# Finger_Tremor_updated1107.net
KiCad netlist of a schematic drawn in Altium Designer
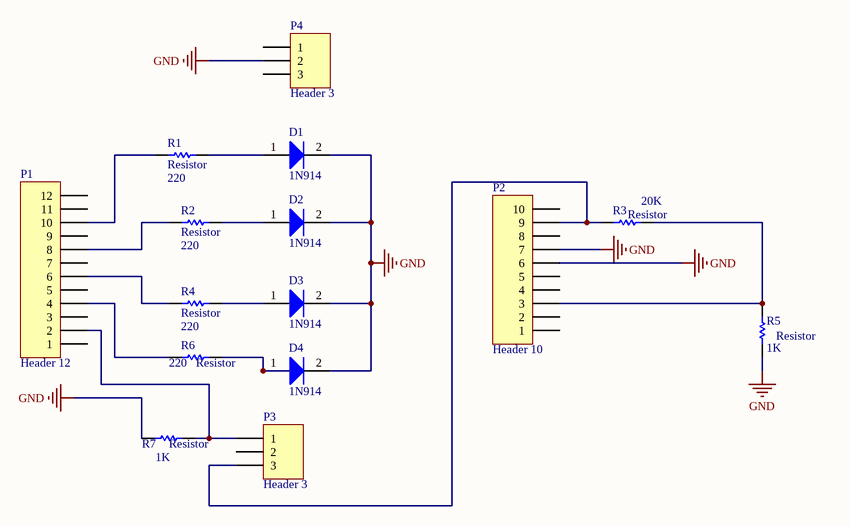
[diagram p0: Finger Tremor_updated1107.SchDoc]

(export (version "E")
  (design (tool "Eeschema 10.0.6"))
  (components
    (comp (ref "D1")
      (value "1N914")
      (footprint "Diode")
      (description "High Conductance Fast Diode")
      (libsource (lib "BME790Library") (part "1N914"))
    )
    (comp (ref "D2")
      (value "1N914")
      (footprint "Diode")
      (description "High Conductance Fast Diode")
      (libsource (lib "BME790Library") (part "1N914"))
    )
    (comp (ref "D3")
      (value "1N914")
      (footprint "Diode")
      (description "High Conductance Fast Diode")
      (libsource (lib "BME790Library") (part "1N914"))
    )
    (comp (ref "D4")
      (value "1N914")
      (footprint "Diode")
      (description "High Conductance Fast Diode")
      (libsource (lib "BME790Library") (part "1N914"))
    )
    (comp (ref "P1")
      (value "Header 12")
      (footprint "HDR1X12")
      (description "Header, 12-Pin")
      (fields (field (name "PUBLISHER") "Altium Limited"))
      (libsource (lib "Miscellaneous Connectors") (part "Header 12"))
    )
    (comp (ref "P2")
      (value "Header 10")
      (footprint "HDR1X10")
      (description "Header, 10-Pin")
      (fields (field (name "PUBLISHER") "Altium Limited"))
      (libsource (lib "Miscellaneous Connectors") (part "Header 10"))
    )
    (comp (ref "P3")
      (value "Header 3")
      (footprint "HDR1X3")
      (description "Header, 3-Pin")
      (fields (field (name "PUBLISHER") "Altium Limited"))
      (libsource (lib "Miscellaneous Connectors") (part "Header 3"))
    )
    (comp (ref "P4")
      (value "Header 3")
      (footprint "HDR1X3")
      (description "Header, 3-Pin")
      (fields (field (name "PUBLISHER") "Altium Limited"))
      (libsource (lib "Miscellaneous Connectors") (part "Header 3"))
    )
    (comp (ref "R1")
      (value "Resistor")
      (footprint "RES")
      (fields (field (name "ALTIUM_VALUE") "220"))
      (libsource (lib "BME790Library") (part "Resistor"))
    )
    (comp (ref "R2")
      (value "Resistor")
      (footprint "RES")
      (fields (field (name "ALTIUM_VALUE") "220"))
      (libsource (lib "BME790Library") (part "Resistor"))
    )
    (comp (ref "R3")
      (value "Resistor")
      (footprint "RES")
      (fields (field (name "ALTIUM_VALUE") "20K"))
      (libsource (lib "BME790Library") (part "Resistor"))
    )
    (comp (ref "R4")
      (value "Resistor")
      (footprint "RES")
      (fields (field (name "ALTIUM_VALUE") "220"))
      (libsource (lib "BME790Library") (part "Resistor"))
    )
    (comp (ref "R5")
      (value "Resistor")
      (footprint "RES")
      (fields (field (name "ALTIUM_VALUE") "1K"))
      (libsource (lib "BME790Library") (part "Resistor"))
    )
    (comp (ref "R6")
      (value "Resistor")
      (footprint "RES")
      (fields (field (name "ALTIUM_VALUE") "220"))
      (libsource (lib "BME790Library") (part "Resistor"))
    )
    (comp (ref "R7")
      (value "Resistor")
      (footprint "RES")
      (fields (field (name "ALTIUM_VALUE") "1K"))
      (libsource (lib "BME790Library") (part "Resistor"))
    )
  )
  (nets
    (net (code "1") (name "GND") (class "Default")
      (node (ref "D1") (pin "2") (pinfunction "K_2") (pintype "passive"))
      (node (ref "D2") (pin "2") (pinfunction "K_2") (pintype "passive"))
      (node (ref "D3") (pin "2") (pinfunction "K_2") (pintype "passive"))
      (node (ref "D4") (pin "2") (pinfunction "K_2") (pintype "passive"))
      (node (ref "P2") (pin "6") (pinfunction "6_6") (pintype "passive"))
      (node (ref "P2") (pin "7") (pinfunction "7_7") (pintype "passive"))
      (node (ref "P4") (pin "2") (pinfunction "2_2") (pintype "passive"))
      (node (ref "R5") (pin "1") (pinfunction "1_1") (pintype "passive"))
      (node (ref "R7") (pin "1") (pinfunction "1_1") (pintype "passive"))
    )
    (net (code "2") (name "Net-(D1-A)") (class "Default")
      (node (ref "D1") (pin "1") (pinfunction "A_1") (pintype "passive"))
      (node (ref "R1") (pin "2") (pinfunction "2_2") (pintype "passive"))
    )
    (net (code "3") (name "Net-(D2-A)") (class "Default")
      (node (ref "D2") (pin "1") (pinfunction "A_1") (pintype "passive"))
      (node (ref "R2") (pin "2") (pinfunction "2_2") (pintype "passive"))
    )
    (net (code "4") (name "Net-(D3-A)") (class "Default")
      (node (ref "D3") (pin "1") (pinfunction "A_1") (pintype "passive"))
      (node (ref "R4") (pin "2") (pinfunction "2_2") (pintype "passive"))
    )
    (net (code "5") (name "Net-(D4-A)") (class "Default")
      (node (ref "D4") (pin "1") (pinfunction "A_1") (pintype "passive"))
      (node (ref "R6") (pin "2") (pinfunction "2_2") (pintype "passive"))
    )
    (net (code "6") (name "Net-(P1-Pad2)") (class "Default")
      (node (ref "P1") (pin "2") (pinfunction "2_2") (pintype "passive"))
      (node (ref "P3") (pin "1") (pinfunction "1_1") (pintype "passive"))
      (node (ref "R7") (pin "2") (pinfunction "2_2") (pintype "passive"))
    )
    (net (code "7") (name "Net-(P1-Pad4)") (class "Default")
      (node (ref "P1") (pin "4") (pinfunction "4_4") (pintype "passive"))
      (node (ref "R6") (pin "1") (pinfunction "1_1") (pintype "passive"))
    )
    (net (code "8") (name "Net-(P1-Pad6)") (class "Default")
      (node (ref "P1") (pin "6") (pinfunction "6_6") (pintype "passive"))
      (node (ref "R4") (pin "1") (pinfunction "1_1") (pintype "passive"))
    )
    (net (code "9") (name "Net-(P1-Pad8)") (class "Default")
      (node (ref "P1") (pin "8") (pinfunction "8_8") (pintype "passive"))
      (node (ref "R2") (pin "1") (pinfunction "1_1") (pintype "passive"))
    )
    (net (code "10") (name "Net-(P1-Pad10)") (class "Default")
      (node (ref "P1") (pin "10") (pinfunction "10_10") (pintype "passive"))
      (node (ref "R1") (pin "1") (pinfunction "1_1") (pintype "passive"))
    )
    (net (code "11") (name "Net-(P2-Pad3)") (class "Default")
      (node (ref "P2") (pin "3") (pinfunction "3_3") (pintype "passive"))
      (node (ref "R3") (pin "2") (pinfunction "2_2") (pintype "passive"))
      (node (ref "R5") (pin "2") (pinfunction "2_2") (pintype "passive"))
    )
    (net (code "12") (name "Net-(P2-Pad9)") (class "Default")
      (node (ref "P2") (pin "9") (pinfunction "9_9") (pintype "passive"))
      (node (ref "P3") (pin "3") (pinfunction "3_3") (pintype "passive"))
      (node (ref "R3") (pin "1") (pinfunction "1_1") (pintype "passive"))
    )
    (net (code "13") (name "unconnected-(P1-Pad1)") (class "Default")
      (node (ref "P1") (pin "1") (pinfunction "1_1") (pintype "passive"))
    )
    (net (code "14") (name "unconnected-(P1-Pad3)") (class "Default")
      (node (ref "P1") (pin "3") (pinfunction "3_3") (pintype "passive"))
    )
    (net (code "15") (name "unconnected-(P1-Pad5)") (class "Default")
      (node (ref "P1") (pin "5") (pinfunction "5_5") (pintype "passive"))
    )
    (net (code "16") (name "unconnected-(P1-Pad7)") (class "Default")
      (node (ref "P1") (pin "7") (pinfunction "7_7") (pintype "passive"))
    )
    (net (code "17") (name "unconnected-(P1-Pad9)") (class "Default")
      (node (ref "P1") (pin "9") (pinfunction "9_9") (pintype "passive"))
    )
    (net (code "18") (name "unconnected-(P1-Pad11)") (class "Default")
      (node (ref "P1") (pin "11") (pinfunction "11_11") (pintype "passive"))
    )
    (net (code "19") (name "unconnected-(P1-Pad12)") (class "Default")
      (node (ref "P1") (pin "12") (pinfunction "12_12") (pintype "passive"))
    )
    (net (code "20") (name "unconnected-(P2-Pad1)") (class "Default")
      (node (ref "P2") (pin "1") (pinfunction "1_1") (pintype "passive"))
    )
    (net (code "21") (name "unconnected-(P2-Pad2)") (class "Default")
      (node (ref "P2") (pin "2") (pinfunction "2_2") (pintype "passive"))
    )
    (net (code "22") (name "unconnected-(P2-Pad4)") (class "Default")
      (node (ref "P2") (pin "4") (pinfunction "4_4") (pintype "passive"))
    )
    (net (code "23") (name "unconnected-(P2-Pad5)") (class "Default")
      (node (ref "P2") (pin "5") (pinfunction "5_5") (pintype "passive"))
    )
    (net (code "24") (name "unconnected-(P2-Pad8)") (class "Default")
      (node (ref "P2") (pin "8") (pinfunction "8_8") (pintype "passive"))
    )
    (net (code "25") (name "unconnected-(P2-Pad10)") (class "Default")
      (node (ref "P2") (pin "10") (pinfunction "10_10") (pintype "passive"))
    )
    (net (code "26") (name "unconnected-(P3-Pad2)") (class "Default")
      (node (ref "P3") (pin "2") (pinfunction "2_2") (pintype "passive"))
    )
    (net (code "27") (name "unconnected-(P4-Pad1)") (class "Default")
      (node (ref "P4") (pin "1") (pinfunction "1_1") (pintype "passive"))
    )
    (net (code "28") (name "unconnected-(P4-Pad3)") (class "Default")
      (node (ref "P4") (pin "3") (pinfunction "3_3") (pintype "passive"))
    )
  )
)
